# 7Seg6digit.net
KiCad netlist of a schematic drawn in EAGLE
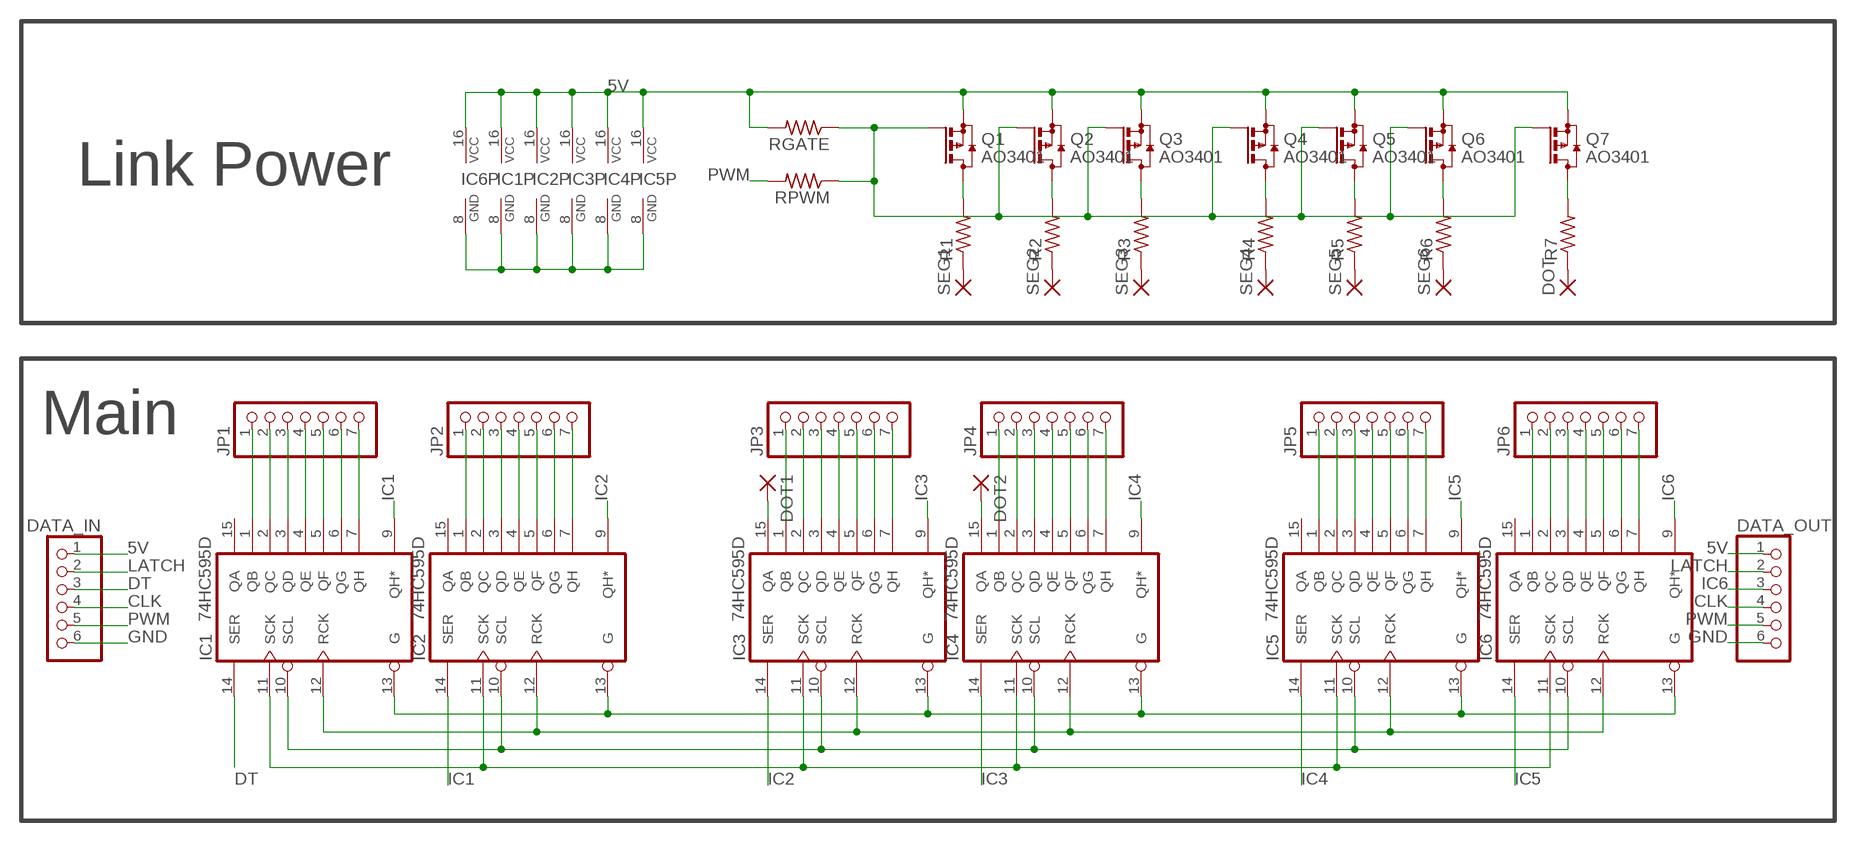
[diagram p0: schematic, sheet 1]

(export (version "E")
  (design (tool "Eeschema 10.0.6"))
  (components
    (comp (ref "DATA_IN")
      (value "PINHD-1X6")
      (footprint "eagle-import:1X06")
      (libsource (lib "eagle-import") (part "PINHD-1X6"))
    )
    (comp (ref "DATA_OUT")
      (value "PINHD-1X6")
      (footprint "eagle-import:1X06")
      (libsource (lib "eagle-import") (part "PINHD-1X6"))
    )
    (comp (ref "DOT")
      (value "SMD2")
      (footprint "eagle-import:SMD1,27-2,54")
      (libsource (lib "eagle-import") (part "SMD2"))
    )
    (comp (ref "DOT1")
      (value "SMD2")
      (footprint "eagle-import:SMD1,27-2,54")
      (libsource (lib "eagle-import") (part "SMD2"))
    )
    (comp (ref "DOT2")
      (value "SMD2")
      (footprint "eagle-import:SMD1,27-2,54")
      (libsource (lib "eagle-import") (part "SMD2"))
    )
    (comp (ref "IC1")
      (value "74HC595D")
      (footprint "eagle-import:SO16")
      (libsource (lib "eagle-import") (part "74595DHC"))
    )
    (comp (ref "IC2")
      (value "74HC595D")
      (footprint "eagle-import:SO16")
      (libsource (lib "eagle-import") (part "74595DHC"))
    )
    (comp (ref "IC3")
      (value "74HC595D")
      (footprint "eagle-import:SO16")
      (libsource (lib "eagle-import") (part "74595DHC"))
    )
    (comp (ref "IC4")
      (value "74HC595D")
      (footprint "eagle-import:SO16")
      (libsource (lib "eagle-import") (part "74595DHC"))
    )
    (comp (ref "IC5")
      (value "74HC595D")
      (footprint "eagle-import:SO16")
      (libsource (lib "eagle-import") (part "74595DHC"))
    )
    (comp (ref "IC6")
      (value "74HC595D")
      (footprint "eagle-import:SO16")
      (libsource (lib "eagle-import") (part "74595DHC"))
    )
    (comp (ref "JP1")
      (value "PINHD-1X7")
      (footprint "eagle-import:1X07")
      (libsource (lib "eagle-import") (part "PINHD-1X7"))
    )
    (comp (ref "JP2")
      (value "PINHD-1X7")
      (footprint "eagle-import:1X07")
      (libsource (lib "eagle-import") (part "PINHD-1X7"))
    )
    (comp (ref "JP3")
      (value "PINHD-1X7")
      (footprint "eagle-import:1X07")
      (libsource (lib "eagle-import") (part "PINHD-1X7"))
    )
    (comp (ref "JP4")
      (value "PINHD-1X7")
      (footprint "eagle-import:1X07")
      (libsource (lib "eagle-import") (part "PINHD-1X7"))
    )
    (comp (ref "JP5")
      (value "PINHD-1X7")
      (footprint "eagle-import:1X07")
      (libsource (lib "eagle-import") (part "PINHD-1X7"))
    )
    (comp (ref "JP6")
      (value "PINHD-1X7")
      (footprint "eagle-import:1X07")
      (libsource (lib "eagle-import") (part "PINHD-1X7"))
    )
    (comp (ref "Q1")
      (value "AO3401")
      (footprint "eagle-import:SOT23")
      (libsource (lib "eagle-import") (part "BSS84"))
    )
    (comp (ref "Q2")
      (value "AO3401")
      (footprint "eagle-import:SOT23")
      (libsource (lib "eagle-import") (part "BSS84"))
    )
    (comp (ref "Q3")
      (value "AO3401")
      (footprint "eagle-import:SOT23")
      (libsource (lib "eagle-import") (part "BSS84"))
    )
    (comp (ref "Q4")
      (value "AO3401")
      (footprint "eagle-import:SOT23")
      (libsource (lib "eagle-import") (part "BSS84"))
    )
    (comp (ref "Q5")
      (value "AO3401")
      (footprint "eagle-import:SOT23")
      (libsource (lib "eagle-import") (part "BSS84"))
    )
    (comp (ref "Q6")
      (value "AO3401")
      (footprint "eagle-import:SOT23")
      (libsource (lib "eagle-import") (part "BSS84"))
    )
    (comp (ref "Q7")
      (value "AO3401")
      (footprint "eagle-import:SOT23")
      (libsource (lib "eagle-import") (part "BSS84"))
    )
    (comp (ref "R1")
      (value "R-US_M1206")
      (footprint "eagle-import:M1206")
      (libsource (lib "eagle-import") (part "R-US_M1206"))
    )
    (comp (ref "R2")
      (value "R-US_M1206")
      (footprint "eagle-import:M1206")
      (libsource (lib "eagle-import") (part "R-US_M1206"))
    )
    (comp (ref "R3")
      (value "R-US_M1206")
      (footprint "eagle-import:M1206")
      (libsource (lib "eagle-import") (part "R-US_M1206"))
    )
    (comp (ref "R4")
      (value "R-US_M1206")
      (footprint "eagle-import:M1206")
      (libsource (lib "eagle-import") (part "R-US_M1206"))
    )
    (comp (ref "R5")
      (value "R-US_M1206")
      (footprint "eagle-import:M1206")
      (libsource (lib "eagle-import") (part "R-US_M1206"))
    )
    (comp (ref "R6")
      (value "R-US_M1206")
      (footprint "eagle-import:M1206")
      (libsource (lib "eagle-import") (part "R-US_M1206"))
    )
    (comp (ref "R7")
      (value "R-US_M1206")
      (footprint "eagle-import:M1206")
      (libsource (lib "eagle-import") (part "R-US_M1206"))
    )
    (comp (ref "RGATE")
      (value "R-US_M1206")
      (footprint "eagle-import:M1206")
      (libsource (lib "eagle-import") (part "R-US_M1206"))
    )
    (comp (ref "RPWM")
      (value "R-US_M1206")
      (footprint "eagle-import:M1206")
      (libsource (lib "eagle-import") (part "R-US_M1206"))
    )
    (comp (ref "SEG1")
      (value "SMD2")
      (footprint "eagle-import:SMD1,27-2,54")
      (libsource (lib "eagle-import") (part "SMD2"))
    )
    (comp (ref "SEG2")
      (value "SMD2")
      (footprint "eagle-import:SMD1,27-2,54")
      (libsource (lib "eagle-import") (part "SMD2"))
    )
    (comp (ref "SEG3")
      (value "SMD2")
      (footprint "eagle-import:SMD1,27-2,54")
      (libsource (lib "eagle-import") (part "SMD2"))
    )
    (comp (ref "SEG4")
      (value "SMD2")
      (footprint "eagle-import:SMD1,27-2,54")
      (libsource (lib "eagle-import") (part "SMD2"))
    )
    (comp (ref "SEG5")
      (value "SMD2")
      (footprint "eagle-import:SMD1,27-2,54")
      (libsource (lib "eagle-import") (part "SMD2"))
    )
    (comp (ref "SEG6")
      (value "SMD2")
      (footprint "eagle-import:SMD1,27-2,54")
      (libsource (lib "eagle-import") (part "SMD2"))
    )
  )
  (nets
    (net (code "1") (name "/5V") (class "Default")
      (node (ref "DATA_IN") (pin "1") (pinfunction "1_1") (pintype "passive"))
      (node (ref "DATA_OUT") (pin "1") (pinfunction "1_1") (pintype "passive"))
      (node (ref "IC1") (pin "10") (pinfunction "SCL_10") (pintype "input"))
      (node (ref "IC1") (pin "16") (pinfunction "VCC_16") (pintype "power_in"))
      (node (ref "IC2") (pin "10") (pinfunction "SCL_10") (pintype "input"))
      (node (ref "IC2") (pin "16") (pinfunction "VCC_16") (pintype "power_in"))
      (node (ref "IC3") (pin "10") (pinfunction "SCL_10") (pintype "input"))
      (node (ref "IC3") (pin "16") (pinfunction "VCC_16") (pintype "power_in"))
      (node (ref "IC4") (pin "10") (pinfunction "SCL_10") (pintype "input"))
      (node (ref "IC4") (pin "16") (pinfunction "VCC_16") (pintype "power_in"))
      (node (ref "IC5") (pin "10") (pinfunction "SCL_10") (pintype "input"))
      (node (ref "IC5") (pin "16") (pinfunction "VCC_16") (pintype "power_in"))
      (node (ref "IC6") (pin "10") (pinfunction "SCL_10") (pintype "input"))
      (node (ref "IC6") (pin "16") (pinfunction "VCC_16") (pintype "power_in"))
      (node (ref "Q1") (pin "2") (pinfunction "S_2") (pintype "passive"))
      (node (ref "Q2") (pin "2") (pinfunction "S_2") (pintype "passive"))
      (node (ref "Q3") (pin "2") (pinfunction "S_2") (pintype "passive"))
      (node (ref "Q4") (pin "2") (pinfunction "S_2") (pintype "passive"))
      (node (ref "Q5") (pin "2") (pinfunction "S_2") (pintype "passive"))
      (node (ref "Q6") (pin "2") (pinfunction "S_2") (pintype "passive"))
      (node (ref "Q7") (pin "2") (pinfunction "S_2") (pintype "passive"))
      (node (ref "RGATE") (pin "2") (pinfunction "2_2") (pintype "passive"))
    )
    (net (code "2") (name "/CLK") (class "Default")
      (node (ref "DATA_IN") (pin "4") (pinfunction "4_4") (pintype "passive"))
      (node (ref "DATA_OUT") (pin "4") (pinfunction "4_4") (pintype "passive"))
      (node (ref "IC1") (pin "11") (pinfunction "SCK_11") (pintype "input"))
      (node (ref "IC2") (pin "11") (pinfunction "SCK_11") (pintype "input"))
      (node (ref "IC3") (pin "11") (pinfunction "SCK_11") (pintype "input"))
      (node (ref "IC4") (pin "11") (pinfunction "SCK_11") (pintype "input"))
      (node (ref "IC5") (pin "11") (pinfunction "SCK_11") (pintype "input"))
      (node (ref "IC6") (pin "11") (pinfunction "SCK_11") (pintype "input"))
    )
    (net (code "3") (name "/DT") (class "Default")
      (node (ref "DATA_IN") (pin "3") (pinfunction "3_3") (pintype "passive"))
      (node (ref "IC1") (pin "14") (pinfunction "SER_14") (pintype "input"))
    )
    (net (code "4") (name "/GND") (class "Default")
      (node (ref "DATA_IN") (pin "6") (pinfunction "6_6") (pintype "passive"))
      (node (ref "DATA_OUT") (pin "6") (pinfunction "6_6") (pintype "passive"))
      (node (ref "IC1") (pin "13") (pinfunction "G_13") (pintype "input"))
      (node (ref "IC1") (pin "8") (pinfunction "GND_8") (pintype "power_in"))
      (node (ref "IC2") (pin "13") (pinfunction "G_13") (pintype "input"))
      (node (ref "IC2") (pin "8") (pinfunction "GND_8") (pintype "power_in"))
      (node (ref "IC3") (pin "13") (pinfunction "G_13") (pintype "input"))
      (node (ref "IC3") (pin "8") (pinfunction "GND_8") (pintype "power_in"))
      (node (ref "IC4") (pin "13") (pinfunction "G_13") (pintype "input"))
      (node (ref "IC4") (pin "8") (pinfunction "GND_8") (pintype "power_in"))
      (node (ref "IC5") (pin "13") (pinfunction "G_13") (pintype "input"))
      (node (ref "IC5") (pin "8") (pinfunction "GND_8") (pintype "power_in"))
      (node (ref "IC6") (pin "13") (pinfunction "G_13") (pintype "input"))
      (node (ref "IC6") (pin "8") (pinfunction "GND_8") (pintype "power_in"))
    )
    (net (code "5") (name "/IC1") (class "Default")
      (node (ref "IC1") (pin "9") (pinfunction "QH*_9") (pintype "tri_state"))
      (node (ref "IC2") (pin "14") (pinfunction "SER_14") (pintype "input"))
    )
    (net (code "6") (name "/IC2") (class "Default")
      (node (ref "IC2") (pin "9") (pinfunction "QH*_9") (pintype "tri_state"))
      (node (ref "IC3") (pin "14") (pinfunction "SER_14") (pintype "input"))
    )
    (net (code "7") (name "/IC3") (class "Default")
      (node (ref "IC3") (pin "9") (pinfunction "QH*_9") (pintype "tri_state"))
      (node (ref "IC4") (pin "14") (pinfunction "SER_14") (pintype "input"))
    )
    (net (code "8") (name "/IC4") (class "Default")
      (node (ref "IC4") (pin "9") (pinfunction "QH*_9") (pintype "tri_state"))
      (node (ref "IC5") (pin "14") (pinfunction "SER_14") (pintype "input"))
    )
    (net (code "9") (name "/IC5") (class "Default")
      (node (ref "IC5") (pin "9") (pinfunction "QH*_9") (pintype "tri_state"))
      (node (ref "IC6") (pin "14") (pinfunction "SER_14") (pintype "input"))
    )
    (net (code "10") (name "/IC6") (class "Default")
      (node (ref "DATA_OUT") (pin "3") (pinfunction "3_3") (pintype "passive"))
      (node (ref "IC6") (pin "9") (pinfunction "QH*_9") (pintype "tri_state"))
    )
    (net (code "11") (name "/LATCH") (class "Default")
      (node (ref "DATA_IN") (pin "2") (pinfunction "2_2") (pintype "passive"))
      (node (ref "DATA_OUT") (pin "2") (pinfunction "2_2") (pintype "passive"))
      (node (ref "IC1") (pin "12") (pinfunction "RCK_12") (pintype "input"))
      (node (ref "IC2") (pin "12") (pinfunction "RCK_12") (pintype "input"))
      (node (ref "IC3") (pin "12") (pinfunction "RCK_12") (pintype "input"))
      (node (ref "IC4") (pin "12") (pinfunction "RCK_12") (pintype "input"))
      (node (ref "IC5") (pin "12") (pinfunction "RCK_12") (pintype "input"))
      (node (ref "IC6") (pin "12") (pinfunction "RCK_12") (pintype "input"))
    )
    (net (code "12") (name "/PWM") (class "Default")
      (node (ref "DATA_IN") (pin "5") (pinfunction "5_5") (pintype "passive"))
      (node (ref "DATA_OUT") (pin "5") (pinfunction "5_5") (pintype "passive"))
      (node (ref "RPWM") (pin "2") (pinfunction "2_2") (pintype "passive"))
    )
    (net (code "13") (name "Net-(DOT-P)") (class "Default")
      (node (ref "DOT") (pin "1") (pinfunction "P_1") (pintype "passive"))
      (node (ref "R7") (pin "1") (pinfunction "1_1") (pintype "passive"))
    )
    (net (code "14") (name "Net-(DOT1-P)") (class "Default")
      (node (ref "DOT1") (pin "1") (pinfunction "P_1") (pintype "passive"))
      (node (ref "IC3") (pin "15") (pinfunction "QA_15") (pintype "tri_state"))
    )
    (net (code "15") (name "Net-(DOT2-P)") (class "Default")
      (node (ref "DOT2") (pin "1") (pinfunction "P_1") (pintype "passive"))
      (node (ref "IC4") (pin "15") (pinfunction "QA_15") (pintype "tri_state"))
    )
    (net (code "16") (name "Net-(IC1A-QB)") (class "Default")
      (node (ref "IC1") (pin "1") (pinfunction "QB_1") (pintype "tri_state"))
      (node (ref "JP1") (pin "1") (pinfunction "1_1") (pintype "passive"))
    )
    (net (code "17") (name "Net-(IC1A-QC)") (class "Default")
      (node (ref "IC1") (pin "2") (pinfunction "QC_2") (pintype "tri_state"))
      (node (ref "JP1") (pin "2") (pinfunction "2_2") (pintype "passive"))
    )
    (net (code "18") (name "Net-(IC1A-QD)") (class "Default")
      (node (ref "IC1") (pin "3") (pinfunction "QD_3") (pintype "tri_state"))
      (node (ref "JP1") (pin "3") (pinfunction "3_3") (pintype "passive"))
    )
    (net (code "19") (name "Net-(IC1A-QE)") (class "Default")
      (node (ref "IC1") (pin "4") (pinfunction "QE_4") (pintype "tri_state"))
      (node (ref "JP1") (pin "4") (pinfunction "4_4") (pintype "passive"))
    )
    (net (code "20") (name "Net-(IC1A-QF)") (class "Default")
      (node (ref "IC1") (pin "5") (pinfunction "QF_5") (pintype "tri_state"))
      (node (ref "JP1") (pin "5") (pinfunction "5_5") (pintype "passive"))
    )
    (net (code "21") (name "Net-(IC1A-QG)") (class "Default")
      (node (ref "IC1") (pin "6") (pinfunction "QG_6") (pintype "tri_state"))
      (node (ref "JP1") (pin "6") (pinfunction "6_6") (pintype "passive"))
    )
    (net (code "22") (name "Net-(IC1A-QH)") (class "Default")
      (node (ref "IC1") (pin "7") (pinfunction "QH_7") (pintype "tri_state"))
      (node (ref "JP1") (pin "7") (pinfunction "7_7") (pintype "passive"))
    )
    (net (code "23") (name "Net-(IC2A-QB)") (class "Default")
      (node (ref "IC2") (pin "1") (pinfunction "QB_1") (pintype "tri_state"))
      (node (ref "JP2") (pin "1") (pinfunction "1_1") (pintype "passive"))
    )
    (net (code "24") (name "Net-(IC2A-QC)") (class "Default")
      (node (ref "IC2") (pin "2") (pinfunction "QC_2") (pintype "tri_state"))
      (node (ref "JP2") (pin "2") (pinfunction "2_2") (pintype "passive"))
    )
    (net (code "25") (name "Net-(IC2A-QD)") (class "Default")
      (node (ref "IC2") (pin "3") (pinfunction "QD_3") (pintype "tri_state"))
      (node (ref "JP2") (pin "3") (pinfunction "3_3") (pintype "passive"))
    )
    (net (code "26") (name "Net-(IC2A-QE)") (class "Default")
      (node (ref "IC2") (pin "4") (pinfunction "QE_4") (pintype "tri_state"))
      (node (ref "JP2") (pin "4") (pinfunction "4_4") (pintype "passive"))
    )
    (net (code "27") (name "Net-(IC2A-QF)") (class "Default")
      (node (ref "IC2") (pin "5") (pinfunction "QF_5") (pintype "tri_state"))
      (node (ref "JP2") (pin "5") (pinfunction "5_5") (pintype "passive"))
    )
    (net (code "28") (name "Net-(IC2A-QG)") (class "Default")
      (node (ref "IC2") (pin "6") (pinfunction "QG_6") (pintype "tri_state"))
      (node (ref "JP2") (pin "6") (pinfunction "6_6") (pintype "passive"))
    )
    (net (code "29") (name "Net-(IC2A-QH)") (class "Default")
      (node (ref "IC2") (pin "7") (pinfunction "QH_7") (pintype "tri_state"))
      (node (ref "JP2") (pin "7") (pinfunction "7_7") (pintype "passive"))
    )
    (net (code "30") (name "Net-(IC3A-QB)") (class "Default")
      (node (ref "IC3") (pin "1") (pinfunction "QB_1") (pintype "tri_state"))
      (node (ref "JP3") (pin "1") (pinfunction "1_1") (pintype "passive"))
    )
    (net (code "31") (name "Net-(IC3A-QC)") (class "Default")
      (node (ref "IC3") (pin "2") (pinfunction "QC_2") (pintype "tri_state"))
      (node (ref "JP3") (pin "2") (pinfunction "2_2") (pintype "passive"))
    )
    (net (code "32") (name "Net-(IC3A-QD)") (class "Default")
      (node (ref "IC3") (pin "3") (pinfunction "QD_3") (pintype "tri_state"))
      (node (ref "JP3") (pin "3") (pinfunction "3_3") (pintype "passive"))
    )
    (net (code "33") (name "Net-(IC3A-QE)") (class "Default")
      (node (ref "IC3") (pin "4") (pinfunction "QE_4") (pintype "tri_state"))
      (node (ref "JP3") (pin "4") (pinfunction "4_4") (pintype "passive"))
    )
    (net (code "34") (name "Net-(IC3A-QF)") (class "Default")
      (node (ref "IC3") (pin "5") (pinfunction "QF_5") (pintype "tri_state"))
      (node (ref "JP3") (pin "5") (pinfunction "5_5") (pintype "passive"))
    )
    (net (code "35") (name "Net-(IC3A-QG)") (class "Default")
      (node (ref "IC3") (pin "6") (pinfunction "QG_6") (pintype "tri_state"))
      (node (ref "JP3") (pin "6") (pinfunction "6_6") (pintype "passive"))
    )
    (net (code "36") (name "Net-(IC3A-QH)") (class "Default")
      (node (ref "IC3") (pin "7") (pinfunction "QH_7") (pintype "tri_state"))
      (node (ref "JP3") (pin "7") (pinfunction "7_7") (pintype "passive"))
    )
    (net (code "37") (name "Net-(IC4A-QB)") (class "Default")
      (node (ref "IC4") (pin "1") (pinfunction "QB_1") (pintype "tri_state"))
      (node (ref "JP4") (pin "1") (pinfunction "1_1") (pintype "passive"))
    )
    (net (code "38") (name "Net-(IC4A-QC)") (class "Default")
      (node (ref "IC4") (pin "2") (pinfunction "QC_2") (pintype "tri_state"))
      (node (ref "JP4") (pin "2") (pinfunction "2_2") (pintype "passive"))
    )
    (net (code "39") (name "Net-(IC4A-QD)") (class "Default")
      (node (ref "IC4") (pin "3") (pinfunction "QD_3") (pintype "tri_state"))
      (node (ref "JP4") (pin "3") (pinfunction "3_3") (pintype "passive"))
    )
    (net (code "40") (name "Net-(IC4A-QE)") (class "Default")
      (node (ref "IC4") (pin "4") (pinfunction "QE_4") (pintype "tri_state"))
      (node (ref "JP4") (pin "4") (pinfunction "4_4") (pintype "passive"))
    )
    (net (code "41") (name "Net-(IC4A-QF)") (class "Default")
      (node (ref "IC4") (pin "5") (pinfunction "QF_5") (pintype "tri_state"))
      (node (ref "JP4") (pin "5") (pinfunction "5_5") (pintype "passive"))
    )
    (net (code "42") (name "Net-(IC4A-QG)") (class "Default")
      (node (ref "IC4") (pin "6") (pinfunction "QG_6") (pintype "tri_state"))
      (node (ref "JP4") (pin "6") (pinfunction "6_6") (pintype "passive"))
    )
    (net (code "43") (name "Net-(IC4A-QH)") (class "Default")
      (node (ref "IC4") (pin "7") (pinfunction "QH_7") (pintype "tri_state"))
      (node (ref "JP4") (pin "7") (pinfunction "7_7") (pintype "passive"))
    )
    (net (code "44") (name "Net-(IC5A-QB)") (class "Default")
      (node (ref "IC5") (pin "1") (pinfunction "QB_1") (pintype "tri_state"))
      (node (ref "JP5") (pin "1") (pinfunction "1_1") (pintype "passive"))
    )
    (net (code "45") (name "Net-(IC5A-QC)") (class "Default")
      (node (ref "IC5") (pin "2") (pinfunction "QC_2") (pintype "tri_state"))
      (node (ref "JP5") (pin "2") (pinfunction "2_2") (pintype "passive"))
    )
    (net (code "46") (name "Net-(IC5A-QD)") (class "Default")
      (node (ref "IC5") (pin "3") (pinfunction "QD_3") (pintype "tri_state"))
      (node (ref "JP5") (pin "3") (pinfunction "3_3") (pintype "passive"))
    )
    (net (code "47") (name "Net-(IC5A-QE)") (class "Default")
      (node (ref "IC5") (pin "4") (pinfunction "QE_4") (pintype "tri_state"))
      (node (ref "JP5") (pin "4") (pinfunction "4_4") (pintype "passive"))
    )
    (net (code "48") (name "Net-(IC5A-QF)") (class "Default")
      (node (ref "IC5") (pin "5") (pinfunction "QF_5") (pintype "tri_state"))
      (node (ref "JP5") (pin "5") (pinfunction "5_5") (pintype "passive"))
    )
    (net (code "49") (name "Net-(IC5A-QG)") (class "Default")
      (node (ref "IC5") (pin "6") (pinfunction "QG_6") (pintype "tri_state"))
      (node (ref "JP5") (pin "6") (pinfunction "6_6") (pintype "passive"))
    )
    (net (code "50") (name "Net-(IC5A-QH)") (class "Default")
      (node (ref "IC5") (pin "7") (pinfunction "QH_7") (pintype "tri_state"))
      (node (ref "JP5") (pin "7") (pinfunction "7_7") (pintype "passive"))
    )
    (net (code "51") (name "Net-(IC6A-QB)") (class "Default")
      (node (ref "IC6") (pin "1") (pinfunction "QB_1") (pintype "tri_state"))
      (node (ref "JP6") (pin "1") (pinfunction "1_1") (pintype "passive"))
    )
    (net (code "52") (name "Net-(IC6A-QC)") (class "Default")
      (node (ref "IC6") (pin "2") (pinfunction "QC_2") (pintype "tri_state"))
      (node (ref "JP6") (pin "2") (pinfunction "2_2") (pintype "passive"))
    )
    (net (code "53") (name "Net-(IC6A-QD)") (class "Default")
      (node (ref "IC6") (pin "3") (pinfunction "QD_3") (pintype "tri_state"))
      (node (ref "JP6") (pin "3") (pinfunction "3_3") (pintype "passive"))
    )
    (net (code "54") (name "Net-(IC6A-QE)") (class "Default")
      (node (ref "IC6") (pin "4") (pinfunction "QE_4") (pintype "tri_state"))
      (node (ref "JP6") (pin "4") (pinfunction "4_4") (pintype "passive"))
    )
    (net (code "55") (name "Net-(IC6A-QF)") (class "Default")
      (node (ref "IC6") (pin "5") (pinfunction "QF_5") (pintype "tri_state"))
      (node (ref "JP6") (pin "5") (pinfunction "5_5") (pintype "passive"))
    )
    (net (code "56") (name "Net-(IC6A-QG)") (class "Default")
      (node (ref "IC6") (pin "6") (pinfunction "QG_6") (pintype "tri_state"))
      (node (ref "JP6") (pin "6") (pinfunction "6_6") (pintype "passive"))
    )
    (net (code "57") (name "Net-(IC6A-QH)") (class "Default")
      (node (ref "IC6") (pin "7") (pinfunction "QH_7") (pintype "tri_state"))
      (node (ref "JP6") (pin "7") (pinfunction "7_7") (pintype "passive"))
    )
    (net (code "58") (name "Net-(Q1-D)") (class "Default")
      (node (ref "Q1") (pin "3") (pinfunction "D_3") (pintype "passive"))
      (node (ref "R1") (pin "2") (pinfunction "2_2") (pintype "passive"))
    )
    (net (code "59") (name "Net-(Q1-G)") (class "Default")
      (node (ref "Q1") (pin "1") (pinfunction "G_1") (pintype "passive"))
      (node (ref "Q2") (pin "1") (pinfunction "G_1") (pintype "passive"))
      (node (ref "Q3") (pin "1") (pinfunction "G_1") (pintype "passive"))
      (node (ref "Q4") (pin "1") (pinfunction "G_1") (pintype "passive"))
      (node (ref "Q5") (pin "1") (pinfunction "G_1") (pintype "passive"))
      (node (ref "Q6") (pin "1") (pinfunction "G_1") (pintype "passive"))
      (node (ref "Q7") (pin "1") (pinfunction "G_1") (pintype "passive"))
      (node (ref "RGATE") (pin "1") (pinfunction "1_1") (pintype "passive"))
      (node (ref "RPWM") (pin "1") (pinfunction "1_1") (pintype "passive"))
    )
    (net (code "60") (name "Net-(Q2-D)") (class "Default")
      (node (ref "Q2") (pin "3") (pinfunction "D_3") (pintype "passive"))
      (node (ref "R2") (pin "2") (pinfunction "2_2") (pintype "passive"))
    )
    (net (code "61") (name "Net-(Q3-D)") (class "Default")
      (node (ref "Q3") (pin "3") (pinfunction "D_3") (pintype "passive"))
      (node (ref "R3") (pin "2") (pinfunction "2_2") (pintype "passive"))
    )
    (net (code "62") (name "Net-(Q4-D)") (class "Default")
      (node (ref "Q4") (pin "3") (pinfunction "D_3") (pintype "passive"))
      (node (ref "R4") (pin "2") (pinfunction "2_2") (pintype "passive"))
    )
    (net (code "63") (name "Net-(Q5-D)") (class "Default")
      (node (ref "Q5") (pin "3") (pinfunction "D_3") (pintype "passive"))
      (node (ref "R5") (pin "2") (pinfunction "2_2") (pintype "passive"))
    )
    (net (code "64") (name "Net-(Q6-D)") (class "Default")
      (node (ref "Q6") (pin "3") (pinfunction "D_3") (pintype "passive"))
      (node (ref "R6") (pin "2") (pinfunction "2_2") (pintype "passive"))
    )
    (net (code "65") (name "Net-(Q7-D)") (class "Default")
      (node (ref "Q7") (pin "3") (pinfunction "D_3") (pintype "passive"))
      (node (ref "R7") (pin "2") (pinfunction "2_2") (pintype "passive"))
    )
    (net (code "66") (name "Net-(SEG1-P)") (class "Default")
      (node (ref "R1") (pin "1") (pinfunction "1_1") (pintype "passive"))
      (node (ref "SEG1") (pin "1") (pinfunction "P_1") (pintype "passive"))
    )
    (net (code "67") (name "Net-(SEG2-P)") (class "Default")
      (node (ref "R2") (pin "1") (pinfunction "1_1") (pintype "passive"))
      (node (ref "SEG2") (pin "1") (pinfunction "P_1") (pintype "passive"))
    )
    (net (code "68") (name "Net-(SEG3-P)") (class "Default")
      (node (ref "R3") (pin "1") (pinfunction "1_1") (pintype "passive"))
      (node (ref "SEG3") (pin "1") (pinfunction "P_1") (pintype "passive"))
    )
    (net (code "69") (name "Net-(SEG4-P)") (class "Default")
      (node (ref "R4") (pin "1") (pinfunction "1_1") (pintype "passive"))
      (node (ref "SEG4") (pin "1") (pinfunction "P_1") (pintype "passive"))
    )
    (net (code "70") (name "Net-(SEG5-P)") (class "Default")
      (node (ref "R5") (pin "1") (pinfunction "1_1") (pintype "passive"))
      (node (ref "SEG5") (pin "1") (pinfunction "P_1") (pintype "passive"))
    )
    (net (code "71") (name "Net-(SEG6-P)") (class "Default")
      (node (ref "R6") (pin "1") (pinfunction "1_1") (pintype "passive"))
      (node (ref "SEG6") (pin "1") (pinfunction "P_1") (pintype "passive"))
    )
    (net (code "72") (name "unconnected-(IC1A-QA-Pad15)") (class "Default")
      (node (ref "IC1") (pin "15") (pinfunction "QA_15") (pintype "tri_state"))
    )
    (net (code "73") (name "unconnected-(IC2A-QA-Pad15)") (class "Default")
      (node (ref "IC2") (pin "15") (pinfunction "QA_15") (pintype "tri_state"))
    )
    (net (code "74") (name "unconnected-(IC5A-QA-Pad15)") (class "Default")
      (node (ref "IC5") (pin "15") (pinfunction "QA_15") (pintype "tri_state"))
    )
    (net (code "75") (name "unconnected-(IC6A-QA-Pad15)") (class "Default")
      (node (ref "IC6") (pin "15") (pinfunction "QA_15") (pintype "tri_state"))
    )
  )
)
